# AFE_OG.net
KiCad netlist of a schematic drawn in Altium Designer
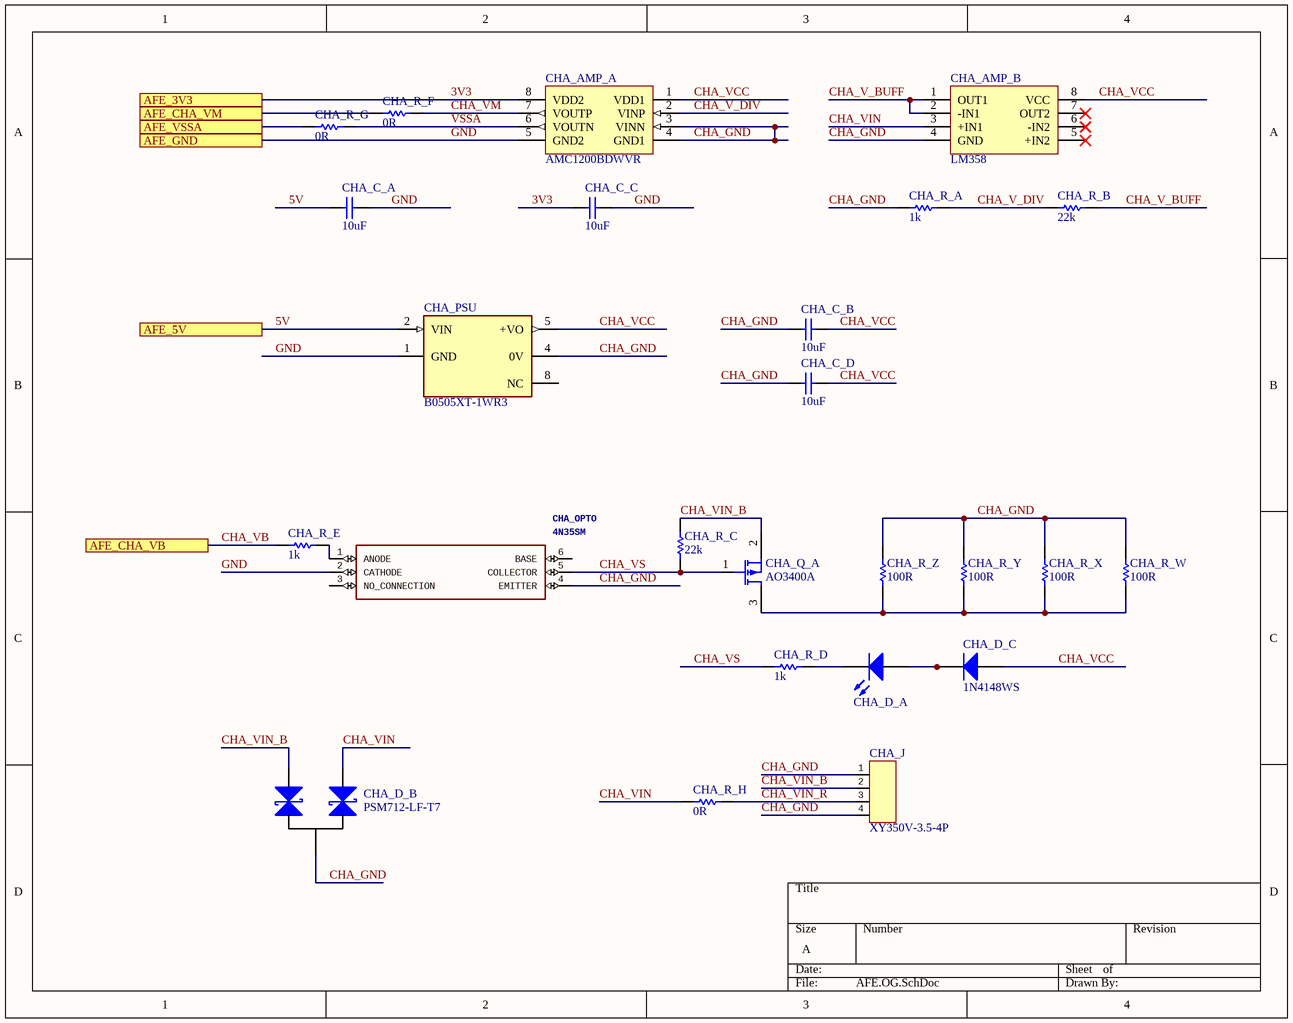
[diagram p0: AFE.OG.SchDoc]

(export (version "E")
  (design (tool "Eeschema 10.0.6"))
  (components
    (comp (ref "CHA_AMP_A")
      (value "AMC1200BDWVR")
      (footprint "FOOTPRINTS:SOIC-8-P1.27-W7.5")
      (description "U - IC - 100KHz ISOLATION AMPLIFIER")
      (fields (field (name "LCSC PART #") "C79905"))
      (libsource (lib "JLC_PCB") (part "AMC1200BDWVR"))
    )
    (comp (ref "CHA_AMP_B")
      (value "LM358")
      (footprint "FOOTPRINTS:SOIC-8-P1.27-W3.5")
      (description "U - IC - OP AMP (DUAL)")
      (fields (field (name "LCSC PART #") "C63813"))
      (libsource (lib "JLC_PCB") (part "LMV358IDR"))
    )
    (comp (ref "CHA_C_A")
      (value "10uF")
      (footprint "C_0603")
      (description "C - CAPACITOR - MLCC - 10uF - 25V - 0603")
      (fields (field (name "LCSC PART #") "C96446") (field (name "Comment") "CL10A106MA8NRNC"))
      (libsource (lib "JLC_PCB") (part "CL10A106MA8NRNC"))
    )
    (comp (ref "CHA_C_B")
      (value "10uF")
      (footprint "C_0603")
      (description "C - CAPACITOR - MLCC - 10uF - 25V - 0603")
      (fields (field (name "LCSC PART #") "C96446") (field (name "Comment") "CL10A106MA8NRNC"))
      (libsource (lib "JLC_PCB") (part "CL10A106MA8NRNC"))
    )
    (comp (ref "CHA_C_C")
      (value "10uF")
      (footprint "C_0603")
      (description "C - CAPACITOR - MLCC - 10uF - 25V - 0603")
      (fields (field (name "LCSC PART #") "C96446") (field (name "Comment") "CL10A106MA8NRNC"))
      (libsource (lib "JLC_PCB") (part "CL10A106MA8NRNC"))
    )
    (comp (ref "CHA_C_D")
      (value "10uF")
      (footprint "C_0603")
      (description "C - CAPACITOR - MLCC - 10uF - 25V - 0603")
      (fields (field (name "LCSC PART #") "C96446") (field (name "Comment") "CL10A106MA8NRNC"))
      (libsource (lib "JLC_PCB") (part "CL10A106MA8NRNC"))
    )
    (comp (ref "CHA_D_A")
      (value "KT-0603R")
      (footprint "D_0603")
      (description "D - LED - 0603 - Red")
      (fields (field (name "LCSC PART #") "C2286"))
      (libsource (lib "JLC_PCB") (part "KT-0603R"))
    )
    (comp (ref "CHA_D_B")
      (value "PSM712-LF-T7")
      (footprint "TO-236AB")
      (description "D - DIODE - TVS x2 - 7.2V")
      (fields (field (name "LCSC PART #") "C32677"))
      (libsource (lib "JLC_PCB") (part "PSM712-LF-T7"))
    )
    (comp (ref "CHA_D_C")
      (value "1N4148WS")
      (footprint "SOD-323")
      (description "D - DIODE - FAST TRR - 100V - 150mA - 4ns")
      (fields (field (name "LCSC PART #") "C2128"))
      (libsource (lib "JLC_PCB") (part "1N4148WS"))
    )
    (comp (ref "CHA_J")
      (value "XY350V-3.5-4P")
      (footprint "XY350V-3.5-4P")
      (description "J - JACK - TERMINAL - 4P - RIGHT - MALE")
      (fields (field (name "LCSC PART #") "C557656"))
      (libsource (lib "JLC_PCB") (part "XY350V-3.5-4P"))
    )
    (comp (ref "CHA_OPTO")
      (value "4N35SM")
      (footprint "SOT254P916X508-6N")
      (description "Q - OPTOCOUPLER - 4170 V - 100% CTR")
      (fields (field (name "LCSC PART #") "C258228"))
      (libsource (lib "JLC_PCB") (part "4N35SM"))
    )
    (comp (ref "CHA_PSU")
      (value "B0505XT-1WR3")
      (footprint "CONV_B0512XT-1WR3")
      (description "T - Isolated Module DC DC Converter 5 -> 5V 200mA - DIP")
      (fields (field (name "LCSC PART #") "C19188495") (field (name "MF") "EVISUN"))
      (libsource (lib "JLC_PCB") (part "B0505XT-1WR3"))
    )
    (comp (ref "CHA_Q_A")
      (value "AO3400A")
      (footprint "TO-236AB")
      (description "Q - TRANSISTOR - MOSFET (P) - 20V - 3.4A - 0.26 Ohm")
      (fields (field (name "LCSC PART #") "C20917"))
      (libsource (lib "JLC_PCB") (part "AO3400A"))
    )
    (comp (ref "CHA_R_A")
      (value "1k")
      (footprint "R_0603")
      (description "R - RESISTOR - SMD - 1k - 1% - 0603")
      (fields (field (name "LCSC PART #") "C21190") (field (name "Comment") "0603WAF1001T5E"))
      (libsource (lib "JLC_PCB") (part "0603WAF1001T5E"))
    )
    (comp (ref "CHA_R_B")
      (value "22k")
      (footprint "R_0603")
      (description "R - RESISTOR - SMD - 22k - 1% - 0603")
      (fields (field (name "LCSC PART #") "C31850") (field (name "Comment") "0603WAF2202T5E"))
      (libsource (lib "JLC_PCB") (part "0603WAF2202T5E"))
    )
    (comp (ref "CHA_R_C")
      (value "22k")
      (footprint "R_0603")
      (description "R - RESISTOR - SMD - 22k - 1% - 0603")
      (fields (field (name "LCSC PART #") "C31850") (field (name "Comment") "0603WAF2202T5E"))
      (libsource (lib "JLC_PCB") (part "0603WAF2202T5E"))
    )
    (comp (ref "CHA_R_D")
      (value "1k")
      (footprint "R_0603")
      (description "R - RESISTOR - SMD - 1k - 1% - 0603")
      (fields (field (name "LCSC PART #") "C21190") (field (name "Comment") "0603WAF1001T5E"))
      (libsource (lib "JLC_PCB") (part "0603WAF1001T5E"))
    )
    (comp (ref "CHA_R_E")
      (value "1k")
      (footprint "R_0603")
      (description "R - RESISTOR - SMD - 1k - 1% - 0603")
      (fields (field (name "LCSC PART #") "C21190") (field (name "Comment") "0603WAF1001T5E"))
      (libsource (lib "JLC_PCB") (part "0603WAF1001T5E"))
    )
    (comp (ref "CHA_R_F")
      (value "0R")
      (footprint "R_0603")
      (description "R - RESISTOR - SMD - 0R - 1% - 0603")
      (fields (field (name "LCSC PART #") "C21189") (field (name "Comment") "0603WAF0000T5E"))
      (libsource (lib "JLC_PCB") (part "0603WAF0000T5E"))
    )
    (comp (ref "CHA_R_G")
      (value "0R")
      (footprint "R_0603")
      (description "R - RESISTOR - SMD - 0R - 1% - 0603")
      (fields (field (name "LCSC PART #") "C21189") (field (name "Comment") "0603WAF0000T5E"))
      (libsource (lib "JLC_PCB") (part "0603WAF0000T5E"))
    )
    (comp (ref "CHA_R_H")
      (value "0R")
      (footprint "R_0603")
      (description "R - RESISTOR - SMD - 0R - 1% - 0603")
      (fields (field (name "LCSC PART #") "C21189") (field (name "Comment") "0603WAF0000T5E"))
      (libsource (lib "JLC_PCB") (part "0603WAF0000T5E"))
    )
    (comp (ref "CHA_R_W")
      (value "100R")
      (footprint "R_1206")
      (description "R - RESISTOR - SMD - 100R - 1% - 1206")
      (fields (field (name "LCSC PART #") "C17901") (field (name "Comment") "1206W4F1000T5E"))
      (libsource (lib "JLC_PCB") (part "1206W4F1000T5E"))
    )
    (comp (ref "CHA_R_X")
      (value "100R")
      (footprint "R_1206")
      (description "R - RESISTOR - SMD - 100R - 1% - 1206")
      (fields (field (name "LCSC PART #") "C17901") (field (name "Comment") "1206W4F1000T5E"))
      (libsource (lib "JLC_PCB") (part "1206W4F1000T5E"))
    )
    (comp (ref "CHA_R_Y")
      (value "100R")
      (footprint "R_1206")
      (description "R - RESISTOR - SMD - 100R - 1% - 1206")
      (fields (field (name "LCSC PART #") "C17901") (field (name "Comment") "1206W4F1000T5E"))
      (libsource (lib "JLC_PCB") (part "1206W4F1000T5E"))
    )
    (comp (ref "CHA_R_Z")
      (value "100R")
      (footprint "R_1206")
      (description "R - RESISTOR - SMD - 100R - 1% - 1206")
      (fields (field (name "LCSC PART #") "C17901") (field (name "Comment") "1206W4F1000T5E"))
      (libsource (lib "JLC_PCB") (part "1206W4F1000T5E"))
    )
  )
  (nets
    (net (code "1") (name "/3V3") (class "Default")
      (node (ref "CHA_AMP_A") (pin "8") (pinfunction "VDD2_8") (pintype "passive"))
      (node (ref "CHA_C_C") (pin "2") (pinfunction "2_2") (pintype "passive"))
    )
    (net (code "2") (name "/5V") (class "Default")
      (node (ref "CHA_C_A") (pin "2") (pinfunction "2_2") (pintype "passive"))
      (node (ref "CHA_PSU") (pin "2") (pinfunction "VIN_2") (pintype "input"))
    )
    (net (code "3") (name "/AFE_CHA_VM") (class "Default")
      (node (ref "CHA_R_F") (pin "1") (pinfunction "1_1") (pintype "passive"))
    )
    (net (code "4") (name "/AFE_VSSA") (class "Default")
      (node (ref "CHA_R_G") (pin "1") (pinfunction "1_1") (pintype "passive"))
    )
    (net (code "5") (name "/CHA_GND") (class "Default")
      (node (ref "CHA_AMP_A") (pin "3") (pinfunction "VINN_3") (pintype "input"))
      (node (ref "CHA_AMP_A") (pin "4") (pinfunction "GND1_4") (pintype "power_in"))
      (node (ref "CHA_AMP_B") (pin "4") (pinfunction "GND_4") (pintype "passive"))
      (node (ref "CHA_C_B") (pin "2") (pinfunction "2_2") (pintype "passive"))
      (node (ref "CHA_C_D") (pin "2") (pinfunction "2_2") (pintype "passive"))
      (node (ref "CHA_D_B") (pin "3") (pinfunction "A_3") (pintype "passive"))
      (node (ref "CHA_J") (pin "1") (pinfunction "1_1") (pintype "passive"))
      (node (ref "CHA_J") (pin "4") (pinfunction "4_4") (pintype "passive"))
      (node (ref "CHA_OPTO") (pin "4") (pinfunction "EMITTER_4") (pintype "bidirectional"))
      (node (ref "CHA_PSU") (pin "4") (pinfunction "0V_4") (pintype "passive"))
      (node (ref "CHA_R_A") (pin "1") (pinfunction "1_1") (pintype "passive"))
      (node (ref "CHA_R_W") (pin "1") (pinfunction "1_1") (pintype "passive"))
      (node (ref "CHA_R_X") (pin "1") (pinfunction "1_1") (pintype "passive"))
      (node (ref "CHA_R_Y") (pin "1") (pinfunction "1_1") (pintype "passive"))
      (node (ref "CHA_R_Z") (pin "1") (pinfunction "1_1") (pintype "passive"))
    )
    (net (code "6") (name "/CHA_VB") (class "Default")
      (node (ref "CHA_R_E") (pin "1") (pinfunction "1_1") (pintype "passive"))
    )
    (net (code "7") (name "/CHA_VCC") (class "Default")
      (node (ref "CHA_AMP_A") (pin "1") (pinfunction "VDD1_1") (pintype "passive"))
      (node (ref "CHA_AMP_B") (pin "8") (pinfunction "VCC_8") (pintype "passive"))
      (node (ref "CHA_C_B") (pin "1") (pinfunction "1_1") (pintype "passive"))
      (node (ref "CHA_C_D") (pin "1") (pinfunction "1_1") (pintype "passive"))
      (node (ref "CHA_D_C") (pin "2") (pinfunction "A_2") (pintype "passive"))
      (node (ref "CHA_PSU") (pin "5") (pinfunction "+VO_5") (pintype "output"))
    )
    (net (code "8") (name "/CHA_VIN") (class "Default")
      (node (ref "CHA_AMP_B") (pin "3") (pinfunction "+IN1_3") (pintype "passive"))
      (node (ref "CHA_D_B") (pin "2") (pinfunction "K_2") (pintype "passive"))
      (node (ref "CHA_R_H") (pin "1") (pinfunction "1_1") (pintype "passive"))
    )
    (net (code "9") (name "/CHA_VIN_B") (class "Default")
      (node (ref "CHA_D_B") (pin "1") (pinfunction "K_1") (pintype "passive"))
      (node (ref "CHA_J") (pin "2") (pinfunction "2_2") (pintype "passive"))
      (node (ref "CHA_Q_A") (pin "2") (pinfunction "S_2") (pintype "passive"))
      (node (ref "CHA_R_C") (pin "2") (pinfunction "2_2") (pintype "passive"))
    )
    (net (code "10") (name "/CHA_VIN_R") (class "Default")
      (node (ref "CHA_J") (pin "3") (pinfunction "3_3") (pintype "passive"))
      (node (ref "CHA_R_H") (pin "2") (pinfunction "2_2") (pintype "passive"))
    )
    (net (code "11") (name "/CHA_VM") (class "Default")
      (node (ref "CHA_AMP_A") (pin "7") (pinfunction "VOUTP_7") (pintype "output"))
      (node (ref "CHA_R_F") (pin "2") (pinfunction "2_2") (pintype "passive"))
    )
    (net (code "12") (name "/CHA_VS") (class "Default")
      (node (ref "CHA_OPTO") (pin "5") (pinfunction "COLLECTOR_5") (pintype "bidirectional"))
      (node (ref "CHA_Q_A") (pin "1") (pinfunction "G_1") (pintype "passive"))
      (node (ref "CHA_R_C") (pin "1") (pinfunction "1_1") (pintype "passive"))
      (node (ref "CHA_R_D") (pin "1") (pinfunction "1_1") (pintype "passive"))
    )
    (net (code "13") (name "/CHA_V_BUFF") (class "Default")
      (node (ref "CHA_AMP_B") (pin "1") (pinfunction "OUT1_1") (pintype "passive"))
      (node (ref "CHA_AMP_B") (pin "2") (pinfunction "-IN1_2") (pintype "passive"))
      (node (ref "CHA_R_B") (pin "2") (pinfunction "2_2") (pintype "passive"))
    )
    (net (code "14") (name "/CHA_V_DIV") (class "Default")
      (node (ref "CHA_AMP_A") (pin "2") (pinfunction "VINP_2") (pintype "input"))
      (node (ref "CHA_R_A") (pin "2") (pinfunction "2_2") (pintype "passive"))
      (node (ref "CHA_R_B") (pin "1") (pinfunction "1_1") (pintype "passive"))
    )
    (net (code "15") (name "/GND") (class "Default")
      (node (ref "CHA_AMP_A") (pin "5") (pinfunction "GND2_5") (pintype "power_in"))
      (node (ref "CHA_C_A") (pin "1") (pinfunction "1_1") (pintype "passive"))
      (node (ref "CHA_C_C") (pin "1") (pinfunction "1_1") (pintype "passive"))
      (node (ref "CHA_OPTO") (pin "2") (pinfunction "CATHODE_2") (pintype "bidirectional"))
      (node (ref "CHA_PSU") (pin "1") (pinfunction "GND_1") (pintype "power_in"))
    )
    (net (code "16") (name "/VSSA") (class "Default")
      (node (ref "CHA_AMP_A") (pin "6") (pinfunction "VOUTN_6") (pintype "output"))
      (node (ref "CHA_R_G") (pin "2") (pinfunction "2_2") (pintype "passive"))
    )
    (net (code "17") (name "Net-(CHA_D_A-A)") (class "Default")
      (node (ref "CHA_D_A") (pin "2") (pinfunction "A_2") (pintype "passive"))
      (node (ref "CHA_D_C") (pin "1") (pinfunction "K_1") (pintype "passive"))
    )
    (net (code "18") (name "Net-(CHA_D_A-K)") (class "Default")
      (node (ref "CHA_D_A") (pin "1") (pinfunction "K_1") (pintype "passive"))
      (node (ref "CHA_R_D") (pin "2") (pinfunction "2_2") (pintype "passive"))
    )
    (net (code "19") (name "Net-(CHA_OPTO-ANODE)") (class "Default")
      (node (ref "CHA_OPTO") (pin "1") (pinfunction "ANODE_1") (pintype "bidirectional"))
      (node (ref "CHA_R_E") (pin "2") (pinfunction "2_2") (pintype "passive"))
    )
    (net (code "20") (name "Net-(CHA_Q_A-D)") (class "Default")
      (node (ref "CHA_Q_A") (pin "3") (pinfunction "D_3") (pintype "passive"))
      (node (ref "CHA_R_W") (pin "2") (pinfunction "2_2") (pintype "passive"))
      (node (ref "CHA_R_X") (pin "2") (pinfunction "2_2") (pintype "passive"))
      (node (ref "CHA_R_Y") (pin "2") (pinfunction "2_2") (pintype "passive"))
      (node (ref "CHA_R_Z") (pin "2") (pinfunction "2_2") (pintype "passive"))
    )
    (net (code "21") (name "unconnected-(CHA_AMP_B-+IN2-Pad5)") (class "Default")
      (node (ref "CHA_AMP_B") (pin "5") (pinfunction "+IN2_5") (pintype "passive+no_connect"))
    )
    (net (code "22") (name "unconnected-(CHA_AMP_B--IN2-Pad6)") (class "Default")
      (node (ref "CHA_AMP_B") (pin "6") (pinfunction "-IN2_6") (pintype "passive+no_connect"))
    )
    (net (code "23") (name "unconnected-(CHA_AMP_B-OUT2-Pad7)") (class "Default")
      (node (ref "CHA_AMP_B") (pin "7") (pinfunction "OUT2_7") (pintype "passive+no_connect"))
    )
    (net (code "24") (name "unconnected-(CHA_OPTO-BASE-Pad6)") (class "Default")
      (node (ref "CHA_OPTO") (pin "6") (pinfunction "BASE_6") (pintype "bidirectional"))
    )
    (net (code "25") (name "unconnected-(CHA_OPTO-NO_CONNECTION-Pad3)") (class "Default")
      (node (ref "CHA_OPTO") (pin "3") (pinfunction "NO_CONNECTION_3") (pintype "bidirectional"))
    )
    (net (code "26") (name "unconnected-(CHA_PSU-NC-Pad8)") (class "Default")
      (node (ref "CHA_PSU") (pin "8") (pinfunction "NC_8") (pintype "passive"))
    )
  )
)
